# DC-DC_24V_To_5V0.net
KiCad netlist of a schematic drawn in Altium Designer
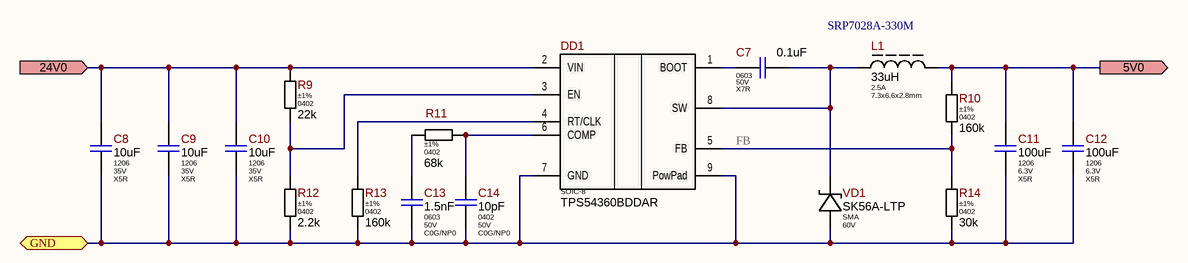
[diagram p0: DC-DC_24V_To_5V0.SchDoc]

(export (version "E")
  (design (tool "Eeschema 10.0.6"))
  (components
    (comp (ref "C7")
      (value "0.1uF")
      (footprint "C_CERAMIC_0603_MED")
      (description "100nF 50V X7R ±10% 0603 Ceramic Capacitor RoHS")
      (fields
        (field (name "PACKAGE") "0603")
        (field (name "VOLTAGE") "50V")
        (field (name "DIELECTRIC TYPE") "X7R")
        (field (name "PART NUMBER") "CL10B104KB8NNNC")
        (field (name "MANUFACTURER") "Samsung Electro-Mechanics")
      )
      (libsource (lib "EL.XXX.T01") (part "Capacitor-NonPolar"))
    )
    (comp (ref "C8")
      (value "10uF")
      (footprint "CAP-1206(3216)X85T15")
      (description "10uF 35V X5R ±10% 1206 Ceramic Capacitor RoHS")
      (fields
        (field (name "PACKAGE") "1206")
        (field (name "VOLTAGE") "35V")
        (field (name "DIELECTRIC TYPE") "X5R")
        (field (name "PART NUMBER") "GRM319R6YA106KA12D")
        (field (name "MANUFACTURER") "Murata Electronics")
      )
      (libsource (lib "EL.XXX.T01") (part "Capacitor-NonPolar"))
    )
    (comp (ref "C9")
      (value "10uF")
      (footprint "CAP-1206(3216)X85T15")
      (description "10uF 35V X5R ±10% 1206 Ceramic Capacitor RoHS")
      (fields
        (field (name "PACKAGE") "1206")
        (field (name "VOLTAGE") "35V")
        (field (name "DIELECTRIC TYPE") "X5R")
        (field (name "PART NUMBER") "GRM319R6YA106KA12D")
        (field (name "MANUFACTURER") "Murata Electronics")
      )
      (libsource (lib "EL.XXX.T01") (part "Capacitor-NonPolar"))
    )
    (comp (ref "C10")
      (value "10uF")
      (footprint "CAP-1206(3216)X85T15")
      (description "10uF 35V X5R ±10% 1206 Ceramic Capacitor RoHS")
      (fields
        (field (name "PACKAGE") "1206")
        (field (name "VOLTAGE") "35V")
        (field (name "DIELECTRIC TYPE") "X5R")
        (field (name "PART NUMBER") "GRM319R6YA106KA12D")
        (field (name "MANUFACTURER") "Murata Electronics")
      )
      (libsource (lib "EL.XXX.T01") (part "Capacitor-NonPolar"))
    )
    (comp (ref "C11")
      (value "100uF")
      (footprint "C_CERAMIC_1206_MED")
      (description "100uF 6.3V X5R ±20% 1206 Ceramic Capacitor RoHS")
      (fields
        (field (name "PACKAGE") "1206")
        (field (name "VOLTAGE") "6.3V")
        (field (name "DIELECTRIC TYPE") "X5R")
        (field (name "PART NUMBER") "CL31A107MQHNNNE")
        (field (name "MANUFACTURER") "Samsung Electro-Mechanics")
      )
      (libsource (lib "EL.XXX.T01") (part "Capacitor-NonPolar"))
    )
    (comp (ref "C12")
      (value "100uF")
      (footprint "C_CERAMIC_1206_MED")
      (description "100uF 6.3V X5R ±20% 1206 Ceramic Capacitor RoHS")
      (fields
        (field (name "PACKAGE") "1206")
        (field (name "VOLTAGE") "6.3V")
        (field (name "DIELECTRIC TYPE") "X5R")
        (field (name "PART NUMBER") "CL31A107MQHNNNE")
        (field (name "MANUFACTURER") "Samsung Electro-Mechanics")
      )
      (libsource (lib "EL.XXX.T01") (part "Capacitor-NonPolar"))
    )
    (comp (ref "C13")
      (value "1.5nF")
      (footprint "C_CERAMIC_0603_MED")
      (description "1.5nF 50V C0G(NP0) ±5% 0603 Ceramic Capacitor RoHS")
      (fields
        (field (name "PACKAGE") "0603")
        (field (name "VOLTAGE") "50V")
        (field (name "DIELECTRIC TYPE") "C0G/NP0")
        (field (name "PART NUMBER") "GRM1885C1H152JA01D")
        (field (name "MANUFACTURER") "Murata Electronics")
      )
      (libsource (lib "EL.XXX.T01") (part "Capacitor-NonPolar"))
    )
    (comp (ref "C14")
      (value "10pF")
      (footprint "C_CERAMIC_0402_MED")
      (description "10pF 50V C0G ±5% 0402 Ceramic Capacitor RoHS")
      (fields
        (field (name "PACKAGE") "0402")
        (field (name "VOLTAGE") "50V")
        (field (name "DIELECTRIC TYPE") "C0G/NP0")
        (field (name "PART NUMBER") "CL05C100JB5NNNC")
        (field (name "MANUFACTURER") "Samsung Electro-Mechanics")
      )
      (libsource (lib "EL.XXX.T01") (part "Capacitor-NonPolar"))
    )
    (comp (ref "DD1")
      (value "TPS54360BDDAR")
      (footprint "SOIC127P620X170_HS-9N")
      (description "60V Input, 3.5A, Step-Down DC/DC Converter With Eco-Mode, SOIC-8 EP")
      (fields
        (field (name "PACKAGE") "SOIC-8")
        (field (name "PART NUMBER") "TPS54360BDDAR")
        (field (name "MANUFACTURER") "Texas Instruments")
      )
      (libsource (lib "EL.XXX.T01") (part "TPS54360B"))
    )
    (comp (ref "L1")
      (value "33uH")
      (footprint "SRP7028A-Series")
      (description "33uH Shielded Wirewound Power Inductor 2.5A 240mOhm Max")
      (fields
        (field (name "CURRENT") "2.5A")
        (field (name "PACKAGE") "7.3x6.6x2.8mm")
        (field (name "PART NUMBER") "SRP7028A-330M")
        (field (name "TOLERANCE") "±20%")
        (field (name "MANUFACTURER") "Bourns Inc")
      )
      (libsource (lib "EL.XXX.T01") (part "Inductor-Ferrite-Fixed"))
    )
    (comp (ref "R9")
      (value "22k")
      (footprint "R_ANY_CHIP_0402_MED")
      (description "22 kOhms ±1% 1/16W 0402 Thick Film Resistor")
      (fields
        (field (name "TOLERANCE") "±1%")
        (field (name "PACKAGE") "0402")
        (field (name "PART NUMBER") "RC0402FR-0722KL")
        (field (name "MANUFACTURER") "Yageo")
      )
      (libsource (lib "EL.XXX.T01") (part "Resistor"))
    )
    (comp (ref "R10")
      (value "160k")
      (footprint "R_ANY_CHIP_0402_MED")
      (description "160 kOhms ±1% 1/16W 0402 Thick Film Resistor")
      (fields
        (field (name "TOLERANCE") "±1%")
        (field (name "PACKAGE") "0402")
        (field (name "PART NUMBER") "RC0402FR-07160KL")
        (field (name "MANUFACTURER") "Yageo")
      )
      (libsource (lib "EL.XXX.T01") (part "Resistor"))
    )
    (comp (ref "R11")
      (value "68k")
      (footprint "R_ANY_CHIP_0402_MED")
      (description "68 kOhms ±1% 1/16W 0402 Thick Film Resistor")
      (fields
        (field (name "TOLERANCE") "±1%")
        (field (name "PACKAGE") "0402")
        (field (name "PART NUMBER") "RC0402FR-0768KL")
        (field (name "MANUFACTURER") "Yageo")
      )
      (libsource (lib "EL.XXX.T01") (part "Resistor"))
    )
    (comp (ref "R12")
      (value "2.2k")
      (footprint "R_ANY_CHIP_0402_MED")
      (description "2.2 kOhms ±1% 1/16W 0402 Thick Film Resistor")
      (fields
        (field (name "TOLERANCE") "±1%")
        (field (name "PACKAGE") "0402")
        (field (name "PART NUMBER") "RC0402FR-072K2L")
        (field (name "MANUFACTURER") "Yageo")
      )
      (libsource (lib "EL.XXX.T01") (part "Resistor"))
    )
    (comp (ref "R13")
      (value "160k")
      (footprint "R_ANY_CHIP_0402_MED")
      (description "160 kOhms ±1% 1/16W 0402 Thick Film Resistor")
      (fields
        (field (name "TOLERANCE") "±1%")
        (field (name "PACKAGE") "0402")
        (field (name "PART NUMBER") "RC0402FR-07160KL")
        (field (name "MANUFACTURER") "Yageo")
      )
      (libsource (lib "EL.XXX.T01") (part "Resistor"))
    )
    (comp (ref "R14")
      (value "30k")
      (footprint "R_ANY_CHIP_0402_MED")
      (description "30 kOhms ±1% 1/16W 0402 Thick Film Resistor")
      (fields
        (field (name "TOLERANCE") "±1%")
        (field (name "PACKAGE") "0402")
        (field (name "PART NUMBER") "RC0402FR-0730KL")
        (field (name "MANUFACTURER") "Yageo")
      )
      (libsource (lib "EL.XXX.T01") (part "Resistor"))
    )
    (comp (ref "VD1")
      (value "SK56A-LTP")
      (footprint "SMA_MED")
      (description "Diode Schottky 60V 5A, SMA")
      (fields
        (field (name "PART NUMBER") "SK56A-LTP")
        (field (name "PACKAGE") "SMA")
        (field (name "VOLTAGE") "60V")
        (field (name "MANUFACTURER") "Micro Commercial Components")
      )
      (libsource (lib "EL.XXX.T01") (part "Diode-Schottky"))
    )
  )
  (nets
    (net (code "1") (name "/5V0") (class "Default")
      (node (ref "C11") (pin "1") (pinfunction "1_1") (pintype "passive"))
      (node (ref "C12") (pin "1") (pinfunction "1_1") (pintype "passive"))
      (node (ref "L1") (pin "2") (pintype "passive"))
      (node (ref "R10") (pin "1") (pintype "passive"))
    )
    (net (code "2") (name "/24V0") (class "Default")
      (node (ref "C10") (pin "1") (pinfunction "1_1") (pintype "passive"))
      (node (ref "C8") (pin "1") (pinfunction "1_1") (pintype "passive"))
      (node (ref "C9") (pin "1") (pinfunction "1_1") (pintype "passive"))
      (node (ref "DD1") (pin "2") (pinfunction "VIN_2") (pintype "passive"))
      (node (ref "R9") (pin "1") (pintype "passive"))
    )
    (net (code "3") (name "/FB") (class "Default")
      (node (ref "DD1") (pin "5") (pinfunction "FB_5") (pintype "passive"))
      (node (ref "R10") (pin "2") (pintype "passive"))
      (node (ref "R14") (pin "1") (pintype "passive"))
    )
    (net (code "4") (name "/GND") (class "Default")
      (node (ref "C10") (pin "2") (pinfunction "2_2") (pintype "passive"))
      (node (ref "C11") (pin "2") (pinfunction "2_2") (pintype "passive"))
      (node (ref "C12") (pin "2") (pinfunction "2_2") (pintype "passive"))
      (node (ref "C13") (pin "1") (pinfunction "1_1") (pintype "passive"))
      (node (ref "C14") (pin "2") (pinfunction "2_2") (pintype "passive"))
      (node (ref "C8") (pin "2") (pinfunction "2_2") (pintype "passive"))
      (node (ref "C9") (pin "2") (pinfunction "2_2") (pintype "passive"))
      (node (ref "DD1") (pin "7") (pinfunction "GND_7") (pintype "passive"))
      (node (ref "DD1") (pin "9") (pinfunction "PowPad_9") (pintype "passive"))
      (node (ref "R12") (pin "2") (pintype "passive"))
      (node (ref "R13") (pin "2") (pintype "passive"))
      (node (ref "R14") (pin "2") (pintype "passive"))
      (node (ref "VD1") (pin "AN") (pintype "passive"))
    )
    (net (code "5") (name "Net-(C13-Pad2)") (class "Default")
      (node (ref "C13") (pin "2") (pinfunction "2_2") (pintype "passive"))
      (node (ref "R11") (pin "2") (pintype "passive"))
    )
    (net (code "6") (name "Net-(DD1-BOOT)") (class "Default")
      (node (ref "C7") (pin "1") (pinfunction "1_1") (pintype "passive"))
      (node (ref "DD1") (pin "1") (pinfunction "BOOT_1") (pintype "passive"))
    )
    (net (code "7") (name "Net-(DD1-COMP)") (class "Default")
      (node (ref "C14") (pin "1") (pinfunction "1_1") (pintype "passive"))
      (node (ref "DD1") (pin "6") (pinfunction "COMP_6") (pintype "passive"))
      (node (ref "R11") (pin "1") (pintype "passive"))
    )
    (net (code "8") (name "Net-(DD1-EN)") (class "Default")
      (node (ref "DD1") (pin "3") (pinfunction "EN_3") (pintype "passive"))
      (node (ref "R12") (pin "1") (pintype "passive"))
      (node (ref "R9") (pin "2") (pintype "passive"))
    )
    (net (code "9") (name "Net-(DD1-RT{slash}CLK)") (class "Default")
      (node (ref "DD1") (pin "4") (pinfunction "RT/CLK_4") (pintype "passive"))
      (node (ref "R13") (pin "1") (pintype "passive"))
    )
    (net (code "10") (name "Net-(DD1-SW)") (class "Default")
      (node (ref "C7") (pin "2") (pinfunction "2_2") (pintype "passive"))
      (node (ref "DD1") (pin "8") (pinfunction "SW_8") (pintype "passive"))
      (node (ref "L1") (pin "1") (pintype "passive"))
      (node (ref "VD1") (pin "CA") (pintype "passive"))
    )
  )
)
